# NexieControl_rev_2.net
KiCad netlist of a schematic drawn in Altium Designer
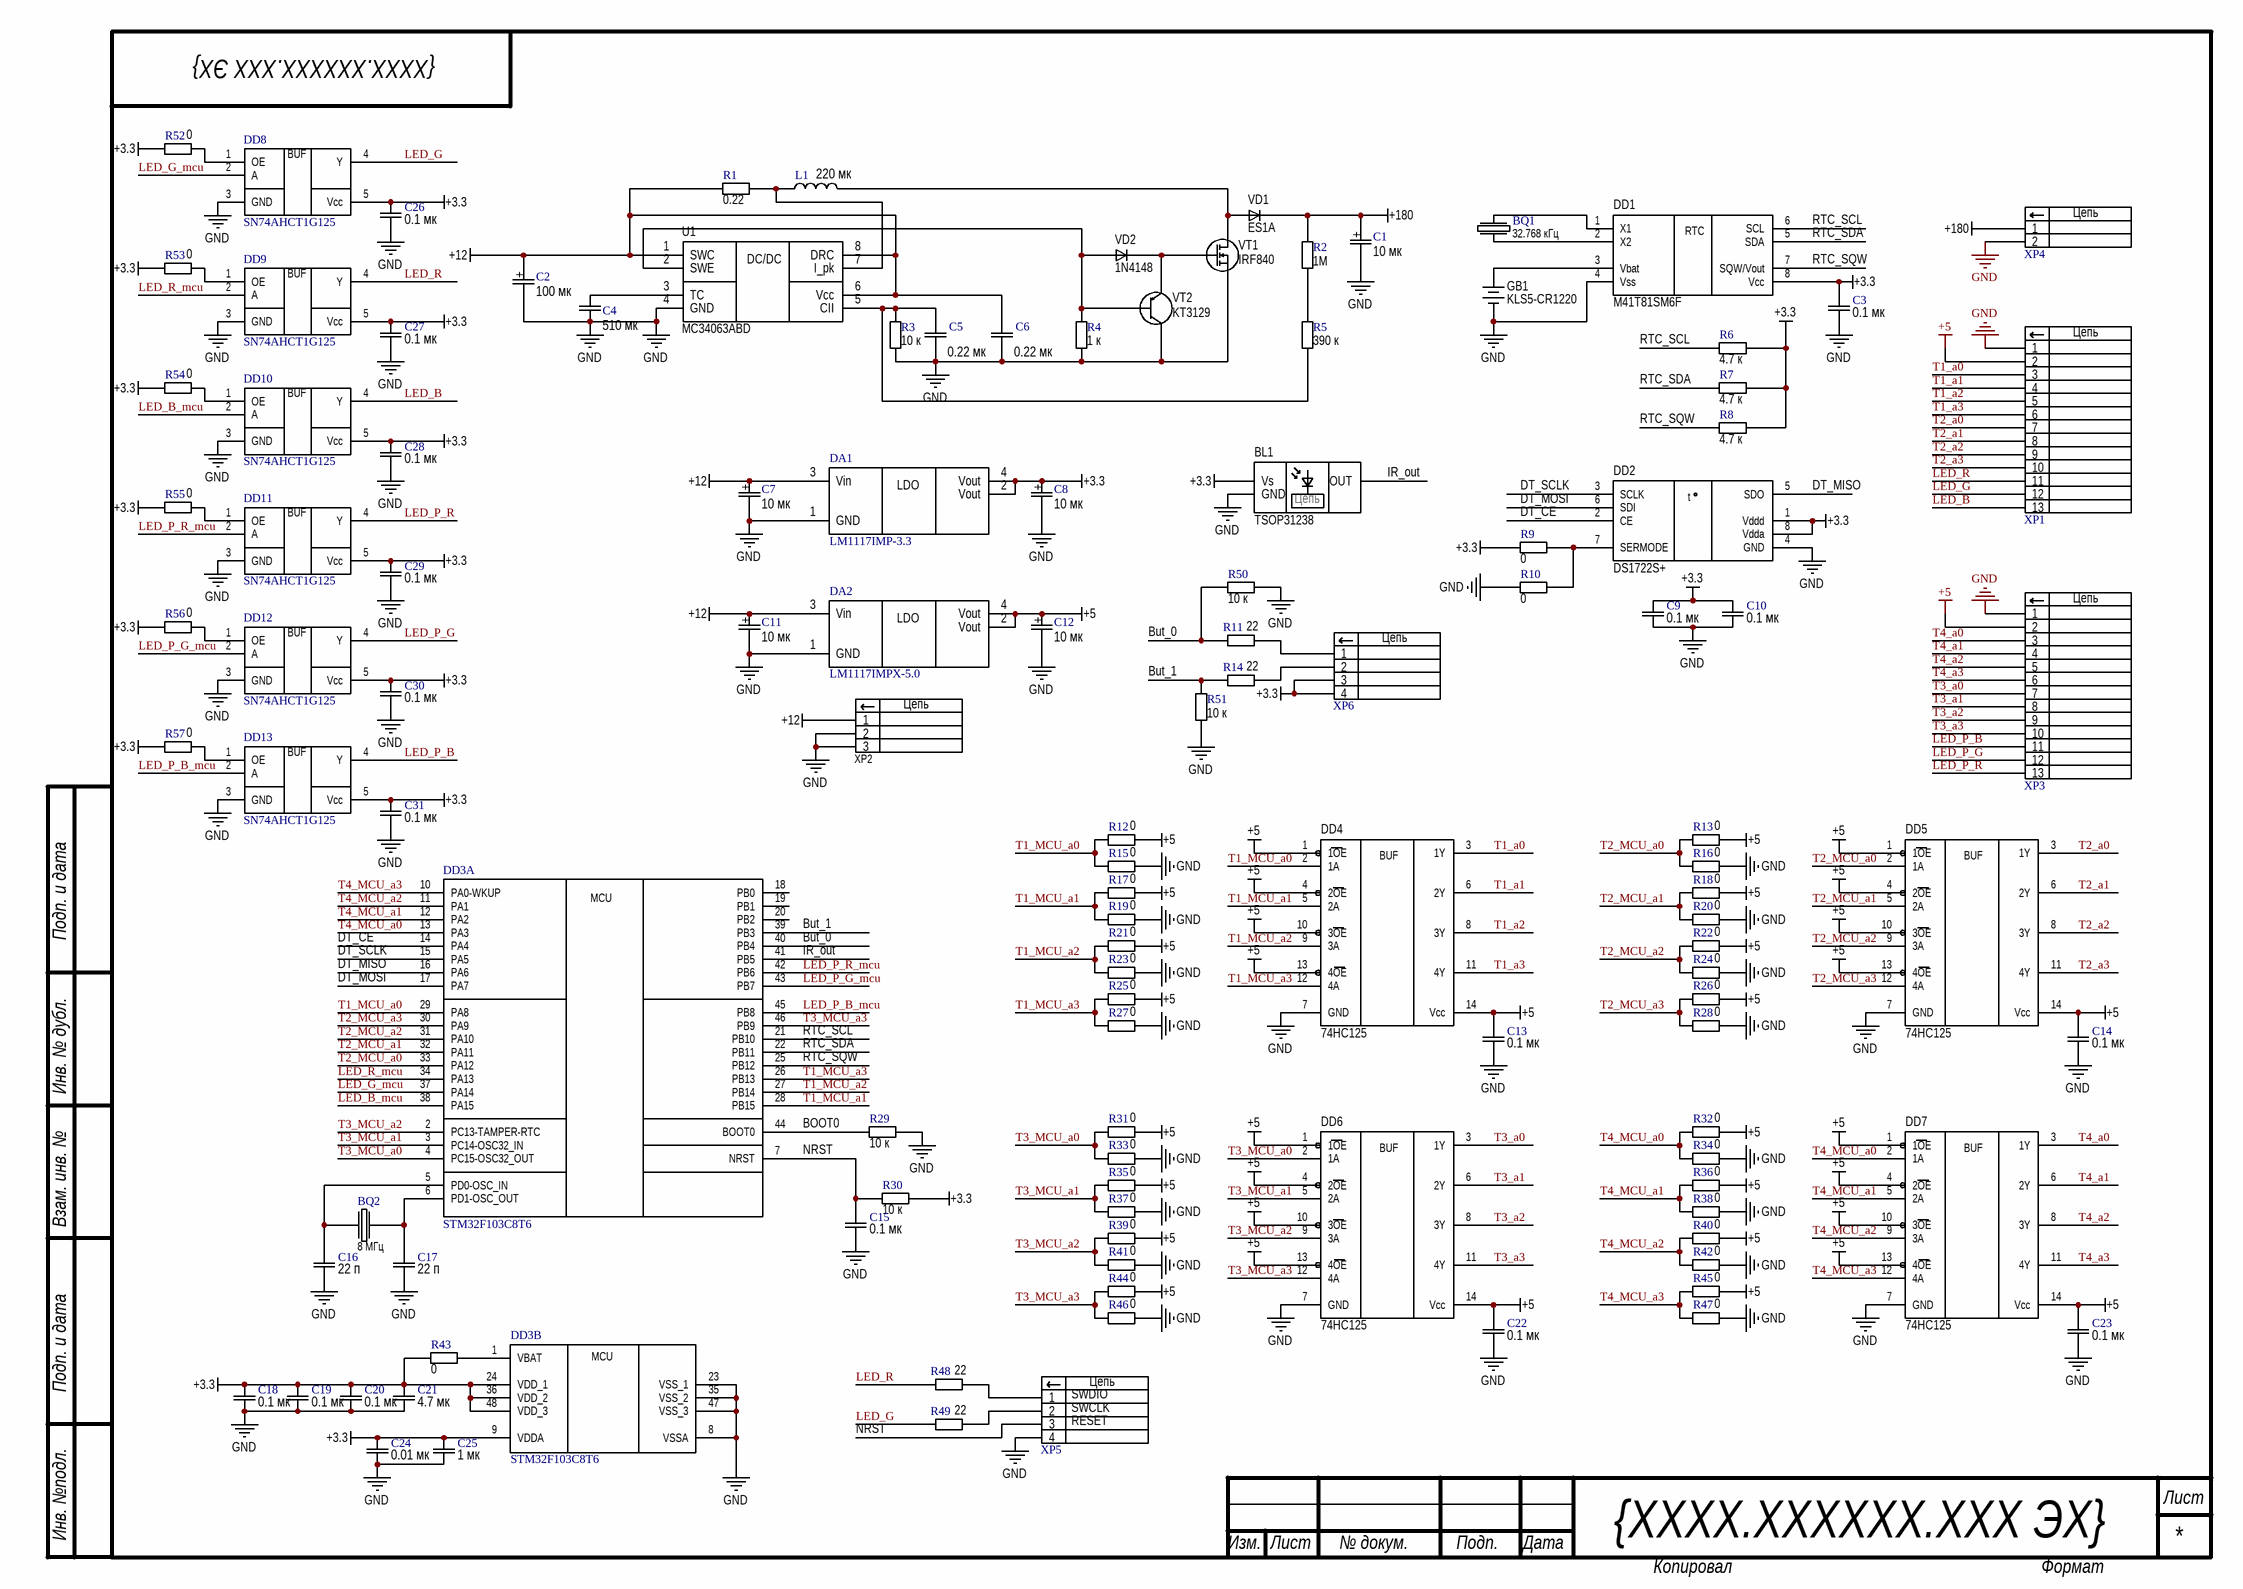
[diagram p0: NexieControl rev.2.SchDoc]

(export (version "E")
  (design (tool "Eeschema 10.0.6"))
  (components
    (comp (ref "BL1")
      (value "TSOP31238")
      (footprint "TSOP31238")
      (description "TSOP31238 (TSOP1738), ИК-приемник 38кГц")
      (fields (field (name "MANUFACTURER") "Vishay") (field (name "CREATOR") "FedorenkoSS"))
      (libsource (lib "Vishay") (part "TSOP31238"))
    )
    (comp (ref "BQ1")
      (value "9HT10")
      (footprint "9HT10")
      (fields
        (field (name "MANUFACTURER") "TXC Corporation")
        (field (name "FREQUENCY") "32.768 кГц")
        (field (name "CREATOR") "FedorenkoSS")
      )
      (libsource (lib "TXC_Corporation") (part "9HT10"))
    )
    (comp (ref "BQ2")
      (value "KX-9AT")
      (footprint "KX-9A")
      (fields
        (field (name "MANUFACTURER") "Geyer Electronic")
        (field (name "FREQUENCY") "8 МГц")
        (field (name "CREATOR") "PavelR")
      )
      (libsource (lib "Geyer") (part "KX-9AT"))
    )
    (comp (ref "C1")
      (value "10 мк")
      (footprint "K50-35(10x12)")
      (fields (field (name "Comment") "Polar capacitor") (field (name "CREATOR") "PavelR"))
      (libsource (lib "Capacitors") (part "Polar capacitor"))
    )
    (comp (ref "C2")
      (value "100 мк")
      (footprint "Tantal_SMD_A")
      (fields
        (field (name "MANUFACTURER") "Vishay")
        (field (name "Comment") "Polar capacitor")
        (field (name "CREATOR") "PavelR")
      )
      (libsource (lib "Capacitors") (part "Polar capacitor"))
    )
    (comp (ref "C3")
      (value "0.1 мк")
      (footprint "SMD_0603")
      (description "Capacitors")
      (fields (field (name "CREATOR") "PavelR"))
      (libsource (lib "Capacitors") (part "Capacitors"))
    )
    (comp (ref "C4")
      (value "510 мк")
      (footprint "SMD_0603")
      (description "Capacitors")
      (fields (field (name "CREATOR") "PavelR"))
      (libsource (lib "Capacitors") (part "Capacitors"))
    )
    (comp (ref "C5")
      (value "0.22 мк")
      (footprint "SMD_0603")
      (description "Capacitors")
      (fields (field (name "CREATOR") "PavelR"))
      (libsource (lib "Capacitors") (part "Capacitors"))
    )
    (comp (ref "C6")
      (value "0.22 мк")
      (footprint "SMD_0603")
      (description "Capacitors")
      (fields (field (name "CREATOR") "PavelR"))
      (libsource (lib "Capacitors") (part "Capacitors"))
    )
    (comp (ref "C7")
      (value "10 мк")
      (footprint "Tantal_SMD_C")
      (fields (field (name "Comment") "Polar capacitor") (field (name "CREATOR") "PavelR"))
      (libsource (lib "Capacitors") (part "Polar capacitor"))
    )
    (comp (ref "C8")
      (value "10 мк")
      (footprint "Tantal_SMD_A")
      (fields (field (name "Comment") "Polar capacitor") (field (name "CREATOR") "PavelR"))
      (libsource (lib "Capacitors") (part "Polar capacitor"))
    )
    (comp (ref "C9")
      (value "0.1 мк")
      (footprint "SMD_0603")
      (description "Capacitors")
      (fields (field (name "CREATOR") "PavelR"))
      (libsource (lib "Capacitors") (part "Capacitors"))
    )
    (comp (ref "C10")
      (value "0.1 мк")
      (footprint "SMD_0603")
      (description "Capacitors")
      (fields (field (name "CREATOR") "PavelR"))
      (libsource (lib "Capacitors") (part "Capacitors"))
    )
    (comp (ref "C11")
      (value "10 мк")
      (footprint "Tantal_SMD_C")
      (fields (field (name "Comment") "Polar capacitor") (field (name "CREATOR") "PavelR"))
      (libsource (lib "Capacitors") (part "Polar capacitor"))
    )
    (comp (ref "C12")
      (value "10 мк")
      (footprint "Tantal_SMD_A")
      (fields (field (name "Comment") "Polar capacitor") (field (name "CREATOR") "PavelR"))
      (libsource (lib "Capacitors") (part "Polar capacitor"))
    )
    (comp (ref "C13")
      (value "0.1 мк")
      (footprint "SMD_0603")
      (description "Capacitors")
      (fields (field (name "CREATOR") "PavelR"))
      (libsource (lib "Capacitors") (part "Capacitors"))
    )
    (comp (ref "C14")
      (value "0.1 мк")
      (footprint "SMD_0603")
      (description "Capacitors")
      (fields (field (name "CREATOR") "PavelR"))
      (libsource (lib "Capacitors") (part "Capacitors"))
    )
    (comp (ref "C15")
      (value "0.1 мк")
      (footprint "SMD_0603")
      (description "Capacitors")
      (fields (field (name "CREATOR") "PavelR"))
      (libsource (lib "Capacitors") (part "Capacitors"))
    )
    (comp (ref "C16")
      (value "22 п")
      (footprint "SMD_0603")
      (description "Capacitors")
      (fields (field (name "CREATOR") "PavelR"))
      (libsource (lib "Capacitors") (part "Capacitors"))
    )
    (comp (ref "C17")
      (value "22 п")
      (footprint "SMD_0603")
      (description "Capacitors")
      (fields (field (name "CREATOR") "PavelR"))
      (libsource (lib "Capacitors") (part "Capacitors"))
    )
    (comp (ref "C18")
      (value "0.1 мк")
      (footprint "SMD_0603")
      (description "Capacitors")
      (fields (field (name "CREATOR") "PavelR"))
      (libsource (lib "Capacitors") (part "Capacitors"))
    )
    (comp (ref "C19")
      (value "0.1 мк")
      (footprint "SMD_0603")
      (description "Capacitors")
      (fields (field (name "CREATOR") "PavelR"))
      (libsource (lib "Capacitors") (part "Capacitors"))
    )
    (comp (ref "C20")
      (value "0.1 мк")
      (footprint "SMD_0603")
      (description "Capacitors")
      (fields (field (name "CREATOR") "PavelR"))
      (libsource (lib "Capacitors") (part "Capacitors"))
    )
    (comp (ref "C21")
      (value "4.7 мк")
      (footprint "SMD_0603")
      (description "Capacitors")
      (fields (field (name "CREATOR") "PavelR"))
      (libsource (lib "Capacitors") (part "Capacitors"))
    )
    (comp (ref "C22")
      (value "0.1 мк")
      (footprint "SMD_0603")
      (description "Capacitors")
      (fields (field (name "CREATOR") "PavelR"))
      (libsource (lib "Capacitors") (part "Capacitors"))
    )
    (comp (ref "C23")
      (value "0.1 мк")
      (footprint "SMD_0603")
      (description "Capacitors")
      (fields (field (name "CREATOR") "PavelR"))
      (libsource (lib "Capacitors") (part "Capacitors"))
    )
    (comp (ref "C24")
      (value "0.01 мк")
      (footprint "SMD_0603")
      (description "Capacitors")
      (fields (field (name "CREATOR") "PavelR"))
      (libsource (lib "Capacitors") (part "Capacitors"))
    )
    (comp (ref "C25")
      (value "1 мк")
      (footprint "SMD_0603")
      (description "Capacitors")
      (fields (field (name "CREATOR") "PavelR"))
      (libsource (lib "Capacitors") (part "Capacitors"))
    )
    (comp (ref "C26")
      (value "0.1 мк")
      (footprint "SMD_0603")
      (description "Capacitors")
      (fields (field (name "CREATOR") "PavelR"))
      (libsource (lib "Capacitors") (part "Capacitors"))
    )
    (comp (ref "C27")
      (value "0.1 мк")
      (footprint "SMD_0603")
      (description "Capacitors")
      (fields (field (name "CREATOR") "PavelR"))
      (libsource (lib "Capacitors") (part "Capacitors"))
    )
    (comp (ref "C28")
      (value "0.1 мк")
      (footprint "SMD_0603")
      (description "Capacitors")
      (fields (field (name "CREATOR") "PavelR"))
      (libsource (lib "Capacitors") (part "Capacitors"))
    )
    (comp (ref "C29")
      (value "0.1 мк")
      (footprint "SMD_0603")
      (description "Capacitors")
      (fields (field (name "CREATOR") "PavelR"))
      (libsource (lib "Capacitors") (part "Capacitors"))
    )
    (comp (ref "C30")
      (value "0.1 мк")
      (footprint "SMD_0603")
      (description "Capacitors")
      (fields (field (name "CREATOR") "PavelR"))
      (libsource (lib "Capacitors") (part "Capacitors"))
    )
    (comp (ref "C31")
      (value "0.1 мк")
      (footprint "SMD_0603")
      (description "Capacitors")
      (fields (field (name "CREATOR") "PavelR"))
      (libsource (lib "Capacitors") (part "Capacitors"))
    )
    (comp (ref "DA1")
      (value "LM1117IMP-3.3")
      (footprint "S-PQFP-G64")
      (description "Стабилизатор напряжения LowDrop, +3.3В, 0.8А [SOT-223]")
      (fields (field (name "MANUFACTURER") "Texas Instruments") (field (name "CREATOR") "FedorenkoS"))
      (libsource (lib "TI_LDO") (part "LM1117IMP-3.3/NOPB"))
    )
    (comp (ref "DA2")
      (value "LM1117IMPX-5.0")
      (footprint "S-PQFP-G64")
      (description "Линейный регулятор с низким падением напряжения, 5В, 1.2А, [SOT-223]")
      (fields (field (name "MANUFACTURER") "Texas Instruments") (field (name "CREATOR") "FedorenkoS"))
      (libsource (lib "TI_LDO") (part "LM1117IMPX-5.0"))
    )
    (comp (ref "DD1")
      (value "M41T81SM6F")
      (footprint "Soic-8")
      (description "Часы реального времени, формат (дата/месяц/год сс:мм:чч), I2C, 2.7В...5.5В, [SOIC-8]")
      (fields (field (name "MANUFACTURER") "ST Microelectronics") (field (name "CREATOR") "FedorenkoSS"))
      (libsource (lib "STMicroelectronics") (part "M41T81SM6F"))
    )
    (comp (ref "DD2")
      (value "DS1722S+")
      (footprint "Soic-8")
      (description "DS1722\r\nDigital Thermometer with\r\nSPI/3-Wire Interface")
      (fields (field (name "MANUFACTURER") "Dallas_Semiconductor") (field (name "CREATOR") "FedorenkoSS"))
      (libsource (lib "Dallas_Semiconductor") (part "DS1722S+"))
    )
    (comp (ref "DD3")
      (value "STM32F103C8T6")
      (footprint "STM-LQFP48L")
      (fields (field (name "MANUFACTURER") "STMicroelectronix"))
      (libsource (lib "STM32F1") (part "STM32F103C8T6"))
    )
    (comp (ref "DD4")
      (value "74HC125")
      (footprint "Soic-14")
      (description "74HC125D.653, Буферы и линейные аппаратные драйверы QUAD 3-STATE BUS BUF [SO-14]")
      (fields (field (name "MANUFACTURER") "NXP Semiconductor") (field (name "CREATOR") "FedorenkoSS"))
      (libsource (lib "NXP_Semiconductor") (part "74HC125"))
    )
    (comp (ref "DD5")
      (value "74HC125")
      (footprint "Soic-14")
      (description "74HC125D.653, Буферы и линейные аппаратные драйверы QUAD 3-STATE BUS BUF [SO-14]")
      (fields (field (name "MANUFACTURER") "NXP Semiconductor") (field (name "CREATOR") "FedorenkoSS"))
      (libsource (lib "NXP_Semiconductor") (part "74HC125"))
    )
    (comp (ref "DD6")
      (value "74HC125")
      (footprint "Soic-14")
      (description "74HC125D.653, Буферы и линейные аппаратные драйверы QUAD 3-STATE BUS BUF [SO-14]")
      (fields (field (name "MANUFACTURER") "NXP Semiconductor") (field (name "CREATOR") "FedorenkoSS"))
      (libsource (lib "NXP_Semiconductor") (part "74HC125"))
    )
    (comp (ref "DD7")
      (value "74HC125")
      (footprint "Soic-14")
      (description "74HC125D.653, Буферы и линейные аппаратные драйверы QUAD 3-STATE BUS BUF [SO-14]")
      (fields (field (name "MANUFACTURER") "NXP Semiconductor") (field (name "CREATOR") "FedorenkoSS"))
      (libsource (lib "NXP_Semiconductor") (part "74HC125"))
    )
    (comp (ref "DD8")
      (value "SN74AHCT1G125")
      (footprint "SOT 23")
      (fields (field (name "MANUFACTURER") "Texas Instruments"))
      (libsource (lib "SN74AHCT1G125") (part "SN74AHCT1G125"))
    )
    (comp (ref "DD9")
      (value "SN74AHCT1G125")
      (footprint "SOT 23")
      (fields (field (name "MANUFACTURER") "Texas Instruments"))
      (libsource (lib "SN74AHCT1G125") (part "SN74AHCT1G125"))
    )
    (comp (ref "DD10")
      (value "SN74AHCT1G125")
      (footprint "SOT 23")
      (fields (field (name "MANUFACTURER") "Texas Instruments"))
      (libsource (lib "SN74AHCT1G125") (part "SN74AHCT1G125"))
    )
    (comp (ref "DD11")
      (value "SN74AHCT1G125")
      (footprint "SOT 23")
      (fields (field (name "MANUFACTURER") "Texas Instruments"))
      (libsource (lib "SN74AHCT1G125") (part "SN74AHCT1G125"))
    )
    (comp (ref "DD12")
      (value "SN74AHCT1G125")
      (footprint "SOT 23")
      (fields (field (name "MANUFACTURER") "Texas Instruments"))
      (libsource (lib "SN74AHCT1G125") (part "SN74AHCT1G125"))
    )
    (comp (ref "DD13")
      (value "SN74AHCT1G125")
      (footprint "SOT 23")
      (fields (field (name "MANUFACTURER") "Texas Instruments"))
      (libsource (lib "SN74AHCT1G125") (part "SN74AHCT1G125"))
    )
    (comp (ref "GB1")
      (value "KLS5-CR1220")
      (footprint "KLS5-CR1220-01")
      (description "KLS5-CR1220-01 (FC1-5010), Батарейный отсек 1xCR1220")
      (fields (field (name "MANUFACTURER") "KLS electronic co ltd") (field (name "CREATOR") "FedorenkoSS"))
      (libsource (lib "Battery") (part "KLS5-CR1220"))
    )
    (comp (ref "L1")
      (value "220 мк")
      (footprint "2220")
      (fields (field (name "Comment") "Inductor") (field (name "CREATER") "FedorenkoS"))
      (libsource (lib "SMD_inductors") (part "Inductor"))
    )
    (comp (ref "R1")
      (value "0.22")
      (footprint "SMD_2512")
      (fields
        (field (name "MANUFACTURER") "Yageo")
        (field (name "Comment") "Resistor")
        (field (name "CREATOR") "PavelR")
      )
      (libsource (lib "") (part "Resistor_1"))
    )
    (comp (ref "R2")
      (value "1М")
      (footprint "SMD_0805")
      (fields (field (name "Comment") "Resistor") (field (name "CREATOR") "PavelR"))
      (libsource (lib "") (part "Resistor_2"))
    )
    (comp (ref "R3")
      (value "10 к")
      (footprint "SMD_0603")
      (fields (field (name "Comment") "Resistor") (field (name "CREATOR") "PavelR"))
      (libsource (lib "") (part "Resistor_2"))
    )
    (comp (ref "R4")
      (value "1 к")
      (footprint "SMD_0603")
      (fields (field (name "Comment") "Resistor") (field (name "CREATOR") "PavelR"))
      (libsource (lib "") (part "Resistor_2"))
    )
    (comp (ref "R5")
      (value "390 к")
      (footprint "SMD_0805")
      (fields (field (name "Comment") "Resistor") (field (name "CREATOR") "PavelR"))
      (libsource (lib "") (part "Resistor_2"))
    )
    (comp (ref "R6")
      (value "4.7 к")
      (footprint "SMD_0603")
      (fields (field (name "Comment") "Resistor") (field (name "CREATOR") "PavelR"))
      (libsource (lib "Resistors") (part "Resistor"))
    )
    (comp (ref "R7")
      (value "4.7 к")
      (footprint "SMD_0603")
      (fields (field (name "Comment") "Resistor") (field (name "CREATOR") "PavelR"))
      (libsource (lib "Resistors") (part "Resistor"))
    )
    (comp (ref "R8")
      (value "4.7 к")
      (footprint "SMD_0603")
      (fields (field (name "Comment") "Resistor") (field (name "CREATOR") "PavelR"))
      (libsource (lib "Resistors") (part "Resistor"))
    )
    (comp (ref "R9")
      (value "0")
      (footprint "SMD_0603")
      (fields (field (name "Comment") "Resistor") (field (name "CREATOR") "PavelR"))
      (libsource (lib "") (part "Resistor_1"))
    )
    (comp (ref "R10")
      (value "0")
      (footprint "SMD_0603")
      (fields (field (name "Comment") "Resistor") (field (name "CREATOR") "PavelR"))
      (libsource (lib "Resistors") (part "Resistor"))
    )
    (comp (ref "R11")
      (value "22")
      (footprint "SMD_0603")
      (fields (field (name "Comment") "Resistor") (field (name "CREATOR") "PavelR"))
      (libsource (lib "Resistors") (part "Resistor"))
    )
    (comp (ref "R12")
      (value "0")
      (footprint "SMD_0603")
      (fields (field (name "Comment") "Resistor") (field (name "CREATOR") "PavelR"))
      (libsource (lib "") (part "Resistor_1"))
    )
    (comp (ref "R13")
      (value "0")
      (footprint "SMD_0603")
      (fields (field (name "Comment") "Resistor") (field (name "CREATOR") "PavelR"))
      (libsource (lib "") (part "Resistor_1"))
    )
    (comp (ref "R14")
      (value "22")
      (footprint "SMD_0603")
      (fields (field (name "Comment") "Resistor") (field (name "CREATOR") "PavelR"))
      (libsource (lib "Resistors") (part "Resistor"))
    )
    (comp (ref "R15")
      (value "0")
      (footprint "SMD_0603")
      (fields (field (name "Comment") "Resistor") (field (name "CREATOR") "PavelR"))
      (libsource (lib "Resistors") (part "Resistor"))
    )
    (comp (ref "R16")
      (value "0")
      (footprint "SMD_0603")
      (fields (field (name "Comment") "Resistor") (field (name "CREATOR") "PavelR"))
      (libsource (lib "Resistors") (part "Resistor"))
    )
    (comp (ref "R17")
      (value "0")
      (footprint "SMD_0603")
      (fields (field (name "Comment") "Resistor") (field (name "CREATOR") "PavelR"))
      (libsource (lib "") (part "Resistor_1"))
    )
    (comp (ref "R18")
      (value "0")
      (footprint "SMD_0603")
      (fields (field (name "Comment") "Resistor") (field (name "CREATOR") "PavelR"))
      (libsource (lib "") (part "Resistor_1"))
    )
    (comp (ref "R19")
      (value "0")
      (footprint "SMD_0603")
      (fields (field (name "Comment") "Resistor") (field (name "CREATOR") "PavelR"))
      (libsource (lib "Resistors") (part "Resistor"))
    )
    (comp (ref "R20")
      (value "0")
      (footprint "SMD_0603")
      (fields (field (name "Comment") "Resistor") (field (name "CREATOR") "PavelR"))
      (libsource (lib "Resistors") (part "Resistor"))
    )
    (comp (ref "R21")
      (value "0")
      (footprint "SMD_0603")
      (fields (field (name "Comment") "Resistor") (field (name "CREATOR") "PavelR"))
      (libsource (lib "") (part "Resistor_1"))
    )
    (comp (ref "R22")
      (value "0")
      (footprint "SMD_0603")
      (fields (field (name "Comment") "Resistor") (field (name "CREATOR") "PavelR"))
      (libsource (lib "") (part "Resistor_1"))
    )
    (comp (ref "R23")
      (value "0")
      (footprint "SMD_0603")
      (fields (field (name "Comment") "Resistor") (field (name "CREATOR") "PavelR"))
      (libsource (lib "Resistors") (part "Resistor"))
    )
    (comp (ref "R24")
      (value "0")
      (footprint "SMD_0603")
      (fields (field (name "Comment") "Resistor") (field (name "CREATOR") "PavelR"))
      (libsource (lib "Resistors") (part "Resistor"))
    )
    (comp (ref "R25")
      (value "0")
      (footprint "SMD_0603")
      (fields (field (name "Comment") "Resistor") (field (name "CREATOR") "PavelR"))
      (libsource (lib "") (part "Resistor_1"))
    )
    (comp (ref "R26")
      (value "0")
      (footprint "SMD_0603")
      (fields (field (name "Comment") "Resistor") (field (name "CREATOR") "PavelR"))
      (libsource (lib "") (part "Resistor_1"))
    )
    (comp (ref "R27")
      (value "0")
      (footprint "SMD_0603")
      (fields (field (name "Comment") "Resistor") (field (name "CREATOR") "PavelR"))
      (libsource (lib "Resistors") (part "Resistor"))
    )
    (comp (ref "R28")
      (value "0")
      (footprint "SMD_0603")
      (fields (field (name "Comment") "Resistor") (field (name "CREATOR") "PavelR"))
      (libsource (lib "Resistors") (part "Resistor"))
    )
    (comp (ref "R29")
      (value "10 к")
      (footprint "SMD_0603")
      (fields (field (name "Comment") "Resistor") (field (name "CREATOR") "PavelR"))
      (libsource (lib "") (part "Resistor_1"))
    )
    (comp (ref "R30")
      (value "10 к")
      (footprint "SMD_0603")
      (fields (field (name "Comment") "Resistor") (field (name "CREATOR") "PavelR"))
      (libsource (lib "Resistors") (part "Resistor"))
    )
    (comp (ref "R31")
      (value "0")
      (footprint "SMD_0603")
      (fields (field (name "Comment") "Resistor") (field (name "CREATOR") "PavelR"))
      (libsource (lib "") (part "Resistor_1"))
    )
    (comp (ref "R32")
      (value "0")
      (footprint "SMD_0603")
      (fields (field (name "Comment") "Resistor") (field (name "CREATOR") "PavelR"))
      (libsource (lib "") (part "Resistor_1"))
    )
    (comp (ref "R33")
      (value "0")
      (footprint "SMD_0603")
      (fields (field (name "Comment") "Resistor") (field (name "CREATOR") "PavelR"))
      (libsource (lib "Resistors") (part "Resistor"))
    )
    (comp (ref "R34")
      (value "0")
      (footprint "SMD_0603")
      (fields (field (name "Comment") "Resistor") (field (name "CREATOR") "PavelR"))
      (libsource (lib "Resistors") (part "Resistor"))
    )
    (comp (ref "R35")
      (value "0")
      (footprint "SMD_0603")
      (fields (field (name "Comment") "Resistor") (field (name "CREATOR") "PavelR"))
      (libsource (lib "") (part "Resistor_1"))
    )
    (comp (ref "R36")
      (value "0")
      (footprint "SMD_0603")
      (fields (field (name "Comment") "Resistor") (field (name "CREATOR") "PavelR"))
      (libsource (lib "") (part "Resistor_1"))
    )
    (comp (ref "R37")
      (value "0")
      (footprint "SMD_0603")
      (fields (field (name "Comment") "Resistor") (field (name "CREATOR") "PavelR"))
      (libsource (lib "Resistors") (part "Resistor"))
    )
    (comp (ref "R38")
      (value "0")
      (footprint "SMD_0603")
      (fields (field (name "Comment") "Resistor") (field (name "CREATOR") "PavelR"))
      (libsource (lib "Resistors") (part "Resistor"))
    )
    (comp (ref "R39")
      (value "0")
      (footprint "SMD_0603")
      (fields (field (name "Comment") "Resistor") (field (name "CREATOR") "PavelR"))
      (libsource (lib "") (part "Resistor_1"))
    )
    (comp (ref "R40")
      (value "0")
      (footprint "SMD_0603")
      (fields (field (name "Comment") "Resistor") (field (name "CREATOR") "PavelR"))
      (libsource (lib "") (part "Resistor_1"))
    )
    (comp (ref "R41")
      (value "0")
      (footprint "SMD_0603")
      (fields (field (name "Comment") "Resistor") (field (name "CREATOR") "PavelR"))
      (libsource (lib "Resistors") (part "Resistor"))
    )
    (comp (ref "R42")
      (value "0")
      (footprint "SMD_0603")
      (fields (field (name "Comment") "Resistor") (field (name "CREATOR") "PavelR"))
      (libsource (lib "Resistors") (part "Resistor"))
    )
    (comp (ref "R43")
      (value "0")
      (footprint "SMD_0603")
      (fields (field (name "Comment") "Resistor") (field (name "CREATOR") "PavelR"))
      (libsource (lib "") (part "Resistor_1"))
    )
    (comp (ref "R44")
      (value "0")
      (footprint "SMD_0603")
      (fields (field (name "Comment") "Resistor") (field (name "CREATOR") "PavelR"))
      (libsource (lib "") (part "Resistor_1"))
    )
    (comp (ref "R45")
      (value "0")
      (footprint "SMD_0603")
      (fields (field (name "Comment") "Resistor") (field (name "CREATOR") "PavelR"))
      (libsource (lib "") (part "Resistor_1"))
    )
    (comp (ref "R46")
      (value "0")
      (footprint "SMD_0603")
      (fields (field (name "Comment") "Resistor") (field (name "CREATOR") "PavelR"))
      (libsource (lib "Resistors") (part "Resistor"))
    )
    (comp (ref "R47")
      (value "0")
      (footprint "SMD_0603")
      (fields (field (name "Comment") "Resistor") (field (name "CREATOR") "PavelR"))
      (libsource (lib "Resistors") (part "Resistor"))
    )
    (comp (ref "R48")
      (value "22")
      (footprint "SMD_0603")
      (fields (field (name "Comment") "Resistor") (field (name "CREATOR") "PavelR"))
      (libsource (lib "Resistors") (part "Resistor"))
    )
    (comp (ref "R49")
      (value "22")
      (footprint "SMD_0603")
      (fields (field (name "Comment") "Resistor") (field (name "CREATOR") "PavelR"))
      (libsource (lib "Resistors") (part "Resistor"))
    )
    (comp (ref "R50")
      (value "10 к")
      (footprint "SMD_0603")
      (fields (field (name "Comment") "Resistor") (field (name "CREATOR") "PavelR"))
      (libsource (lib "") (part "Resistor_1"))
    )
    (comp (ref "R51")
      (value "10 к")
      (footprint "SMD_0603")
      (fields (field (name "Comment") "Resistor") (field (name "CREATOR") "PavelR"))
      (libsource (lib "") (part "Resistor_2"))
    )
    (comp (ref "R52")
      (value "0")
      (footprint "SMD_0603")
      (fields (field (name "Comment") "Resistor") (field (name "CREATOR") "PavelR"))
      (libsource (lib "") (part "Resistor_1"))
    )
    (comp (ref "R53")
      (value "0")
      (footprint "SMD_0603")
      (fields (field (name "Comment") "Resistor") (field (name "CREATOR") "PavelR"))
      (libsource (lib "") (part "Resistor_1"))
    )
    (comp (ref "R54")
      (value "0")
      (footprint "SMD_0603")
      (fields (field (name "Comment") "Resistor") (field (name "CREATOR") "PavelR"))
      (libsource (lib "") (part "Resistor_1"))
    )
    (comp (ref "R55")
      (value "0")
      (footprint "SMD_0603")
      (fields (field (name "Comment") "Resistor") (field (name "CREATOR") "PavelR"))
      (libsource (lib "") (part "Resistor_1"))
    )
    (comp (ref "R56")
      (value "0")
      (footprint "SMD_0603")
      (fields (field (name "Comment") "Resistor") (field (name "CREATOR") "PavelR"))
      (libsource (lib "") (part "Resistor_1"))
    )
    (comp (ref "R57")
      (value "0")
      (footprint "SMD_0603")
      (fields (field (name "Comment") "Resistor") (field (name "CREATOR") "PavelR"))
      (libsource (lib "") (part "Resistor_1"))
    )
    (comp (ref "U1")
      (value "MC34063ABD")
      (footprint "SO-8")
      (fields (field (name "MANUFACTURER") "ST Microelectronics"))
      (libsource (lib "STM_DC-DC") (part "MC34063ABD"))
    )
    (comp (ref "VD1")
      (value "ES1A")
      (footprint "DO_214AC")
      (description "ES1J, Диод быстродействующий 1А 600В 35нс [SMA / DO-214AC]")
      (fields (field (name "MANUFACTURER") "DC COMPONENTS CO., LTD.") (field (name "CREATOR") "FedorenkoSS"))
      (libsource (lib "Diodes") (part "ES1A"))
    )
    (comp (ref "VD2")
      (value "1N4148")
      (footprint "SOD-323")
      (fields (field (name "MANUFACTURER") "Vishay") (field (name "CREATOR") "FedorenkoSS"))
      (libsource (lib "Diodes") (part "1N4148"))
    )
    (comp (ref "VT1")
      (value "IRF840")
      (footprint "D2_PAK")
      (description "Транзистор, N-канал 500В 8.0А")
      (fields (field (name "MANUFACTURER") "Vishay") (field (name "CREATOR") "FedorenkoS"))
      (libsource (lib "Tranzistors") (part "IRF840ASPBF"))
    )
    (comp (ref "VT2")
      (value "KT3129")
      (footprint "SOT-23")
      (fields (field (name "MANUFACTURER") "Россия") (field (name "CREATOR") "FedorenkoS"))
      (libsource (lib "Tranzistors") (part "KT3129"))
    )
    (comp (ref "XP1")
      (value "DS1021-1*13SF11")
      (footprint "DS1021-1*13")
      (description "PLS")
      (fields (field (name "РАЗРАБОТЧИК БИБЛИОТЕКИ") "Федоренко С.С."))
      (libsource (lib "Connectors") (part "DS1021-1*13SF11"))
    )
    (comp (ref "XP2")
      (value "Power_jack")
      (footprint "DC_Power_Jack")
      (libsource (lib "Connectors") (part "Power_jack"))
    )
    (comp (ref "XP3")
      (value "DS1021-1*13SF11")
      (footprint "DS1021-1*13")
      (description "PLS")
      (fields (field (name "РАЗРАБОТЧИК БИБЛИОТЕКИ") "Федоренко С.С."))
      (libsource (lib "Connectors") (part "DS1021-1*13SF11"))
    )
    (comp (ref "XP4")
      (value "DS1021-1*2SF11")
      (footprint "DS1021-1*2")
      (description "PLS")
      (fields (field (name "РАЗРАБОТЧИК БИБЛИОТЕКИ") "Федоренко С.С."))
      (libsource (lib "Connectors") (part "DS1021-1*2SF11"))
    )
    (comp (ref "XP5")
      (value "DS1021-1*4SF11")
      (footprint "DS1021-1*4")
      (description "PLS")
      (fields (field (name "РАЗРАБОТЧИК БИБЛИОТЕКИ") "Федоренко С.С."))
      (libsource (lib "Connectors") (part "DS1021-1*4SF11"))
    )
    (comp (ref "XP6")
      (value "DS1021-1*4SF11")
      (footprint "DS1021-1*4")
      (description "PLS")
      (fields (field (name "РАЗРАБОТЧИК БИБЛИОТЕКИ") "Федоренко С.С."))
      (libsource (lib "Connectors") (part "DS1021-1*4SF11"))
    )
  )
  (nets
    (net (code "1") (name "+3.3") (class "Default")
      (node (ref "BL1") (pin "2") (pinfunction "Vs_2") (pintype "passive"))
      (node (ref "C10") (pin "2") (pinfunction "2_2") (pintype "passive"))
      (node (ref "C18") (pin "2") (pinfunction "2_2") (pintype "passive"))
      (node (ref "C19") (pin "2") (pinfunction "2_2") (pintype "passive"))
      (node (ref "C20") (pin "2") (pinfunction "2_2") (pintype "passive"))
      (node (ref "C21") (pin "2") (pinfunction "2_2") (pintype "passive"))
      (node (ref "C24") (pin "2") (pinfunction "2_2") (pintype "passive"))
      (node (ref "C25") (pin "2") (pinfunction "2_2") (pintype "passive"))
      (node (ref "C26") (pin "2") (pinfunction "2_2") (pintype "passive"))
      (node (ref "C27") (pin "2") (pinfunction "2_2") (pintype "passive"))
      (node (ref "C28") (pin "2") (pinfunction "2_2") (pintype "passive"))
      (node (ref "C29") (pin "2") (pinfunction "2_2") (pintype "passive"))
      (node (ref "C3") (pin "2") (pinfunction "2_2") (pintype "passive"))
      (node (ref "C30") (pin "2") (pinfunction "2_2") (pintype "passive"))
      (node (ref "C31") (pin "2") (pinfunction "2_2") (pintype "passive"))
      (node (ref "C8") (pin "1") (pinfunction "1_1") (pintype "passive"))
      (node (ref "C9") (pin "2") (pinfunction "2_2") (pintype "passive"))
      (node (ref "DA1") (pin "2") (pinfunction "Vout_2") (pintype "passive"))
      (node (ref "DA1") (pin "4") (pinfunction "Vout_4") (pintype "passive"))
      (node (ref "DD1") (pin "8") (pinfunction "Vcc_8") (pintype "power_in"))
      (node (ref "DD10") (pin "5") (pinfunction "Vcc_5") (pintype "passive"))
      (node (ref "DD11") (pin "5") (pinfunction "Vcc_5") (pintype "passive"))
      (node (ref "DD12") (pin "5") (pinfunction "Vcc_5") (pintype "passive"))
      (node (ref "DD13") (pin "5") (pinfunction "Vcc_5") (pintype "passive"))
      (node (ref "DD2") (pin "1") (pinfunction "Vddd_1") (pintype "power_in"))
      (node (ref "DD2") (pin "8") (pinfunction "Vdda_8") (pintype "power_in"))
      (node (ref "DD3") (pin "24") (pinfunction "VDD_1_24") (pintype "power_in"))
      (node (ref "DD3") (pin "36") (pinfunction "VDD_2_36") (pintype "power_in"))
      (node (ref "DD3") (pin "48") (pinfunction "VDD_3_48") (pintype "power_in"))
      (node (ref "DD3") (pin "9") (pinfunction "VDDA_9") (pintype "power_in"))
      (node (ref "DD8") (pin "5") (pinfunction "Vcc_5") (pintype "passive"))
      (node (ref "DD9") (pin "5") (pinfunction "Vcc_5") (pintype "passive"))
      (node (ref "R30") (pin "1") (pinfunction "1_1") (pintype "passive"))
      (node (ref "R43") (pin "1") (pinfunction "1_1") (pintype "passive"))
      (node (ref "R52") (pin "1") (pinfunction "1_1") (pintype "passive"))
      (node (ref "R53") (pin "1") (pinfunction "1_1") (pintype "passive"))
      (node (ref "R54") (pin "1") (pinfunction "1_1") (pintype "passive"))
      (node (ref "R55") (pin "1") (pinfunction "1_1") (pintype "passive"))
      (node (ref "R56") (pin "1") (pinfunction "1_1") (pintype "passive"))
      (node (ref "R57") (pin "1") (pinfunction "1_1") (pintype "passive"))
      (node (ref "R6") (pin "1") (pinfunction "1_1") (pintype "passive"))
      (node (ref "R7") (pin "1") (pinfunction "1_1") (pintype "passive"))
      (node (ref "R8") (pin "1") (pinfunction "1_1") (pintype "passive"))
      (node (ref "R9") (pin "1") (pinfunction "1_1") (pintype "passive"))
      (node (ref "XP6") (pin "3") (pinfunction "3_3") (pintype "passive"))
      (node (ref "XP6") (pin "4") (pinfunction "4_4") (pintype "passive"))
    )
    (net (code "2") (name "+5") (class "Default")
      (node (ref "C12") (pin "1") (pinfunction "1_1") (pintype "passive"))
      (node (ref "C13") (pin "2") (pinfunction "2_2") (pintype "passive"))
      (node (ref "C14") (pin "2") (pinfunction "2_2") (pintype "passive"))
      (node (ref "C22") (pin "2") (pinfunction "2_2") (pintype "passive"))
      (node (ref "C23") (pin "2") (pinfunction "2_2") (pintype "passive"))
      (node (ref "DA2") (pin "2") (pinfunction "Vout_2") (pintype "passive"))
      (node (ref "DA2") (pin "4") (pinfunction "Vout_4") (pintype "passive"))
      (node (ref "DD4") (pin "1") (pinfunction "1OE_1") (pintype "power_in"))
      (node (ref "DD4") (pin "10") (pinfunction "3OE_10") (pintype "power_in"))
      (node (ref "DD4") (pin "13") (pinfunction "4OE_13") (pintype "power_in"))
      (node (ref "DD4") (pin "14") (pinfunction "Vcc_14") (pintype "power_in"))
      (node (ref "DD4") (pin "4") (pinfunction "2OE_4") (pintype "power_in"))
      (node (ref "DD5") (pin "1") (pinfunction "1OE_1") (pintype "power_in"))
      (node (ref "DD5") (pin "10") (pinfunction "3OE_10") (pintype "power_in"))
      (node (ref "DD5") (pin "13") (pinfunction "4OE_13") (pintype "power_in"))
      (node (ref "DD5") (pin "14") (pinfunction "Vcc_14") (pintype "power_in"))
      (node (ref "DD5") (pin "4") (pinfunction "2OE_4") (pintype "power_in"))
      (node (ref "DD6") (pin "1") (pinfunction "1OE_1") (pintype "power_in"))
      (node (ref "DD6") (pin "10") (pinfunction "3OE_10") (pintype "power_in"))
      (node (ref "DD6") (pin "13") (pinfunction "4OE_13") (pintype "power_in"))
      (node (ref "DD6") (pin "14") (pinfunction "Vcc_14") (pintype "power_in"))
      (node (ref "DD6") (pin "4") (pinfunction "2OE_4") (pintype "power_in"))
      (node (ref "DD7") (pin "1") (pinfunction "1OE_1") (pintype "power_in"))
      (node (ref "DD7") (pin "10") (pinfunction "3OE_10") (pintype "power_in"))
      (node (ref "DD7") (pin "13") (pinfunction "4OE_13") (pintype "power_in"))
      (node (ref "DD7") (pin "14") (pinfunction "Vcc_14") (pintype "power_in"))
      (node (ref "DD7") (pin "4") (pinfunction "2OE_4") (pintype "power_in"))
      (node (ref "R12") (pin "2") (pinfunction "2_2") (pintype "passive"))
      (node (ref "R13") (pin "2") (pinfunction "2_2") (pintype "passive"))
      (node (ref "R17") (pin "2") (pinfunction "2_2") (pintype "passive"))
      (node (ref "R18") (pin "2") (pinfunction "2_2") (pintype "passive"))
      (node (ref "R21") (pin "2") (pinfunction "2_2") (pintype "passive"))
      (node (ref "R22") (pin "2") (pinfunction "2_2") (pintype "passive"))
      (node (ref "R25") (pin "2") (pinfunction "2_2") (pintype "passive"))
      (node (ref "R26") (pin "2") (pinfunction "2_2") (pintype "passive"))
      (node (ref "R31") (pin "2") (pinfunction "2_2") (pintype "passive"))
      (node (ref "R32") (pin "2") (pinfunction "2_2") (pintype "passive"))
      (node (ref "R35") (pin "2") (pinfunction "2_2") (pintype "passive"))
      (node (ref "R36") (pin "2") (pinfunction "2_2") (pintype "passive"))
      (node (ref "R39") (pin "2") (pinfunction "2_2") (pintype "passive"))
      (node (ref "R40") (pin "2") (pinfunction "2_2") (pintype "passive"))
      (node (ref "R44") (pin "2") (pinfunction "2_2") (pintype "passive"))
      (node (ref "R45") (pin "2") (pinfunction "2_2") (pintype "passive"))
      (node (ref "XP1") (pin "2") (pinfunction "2_2") (pintype "passive"))
      (node (ref "XP3") (pin "2") (pinfunction "2_2") (pintype "passive"))
    )
    (net (code "3") (name "+12") (class "Default")
      (node (ref "C11") (pin "1") (pinfunction "1_1") (pintype "passive"))
      (node (ref "C2") (pin "1") (pinfunction "1_1") (pintype "passive"))
      (node (ref "C6") (pin "2") (pinfunction "2_2") (pintype "passive"))
      (node (ref "C7") (pin "1") (pinfunction "1_1") (pintype "passive"))
      (node (ref "DA1") (pin "3") (pinfunction "Vin_3") (pintype "passive"))
      (node (ref "DA2") (pin "3") (pinfunction "Vin_3") (pintype "passive"))
      (node (ref "R1") (pin "1") (pinfunction "1_1") (pintype "passive"))
      (node (ref "U1") (pin "1") (pinfunction "SWC_1") (pintype "passive"))
      (node (ref "U1") (pin "6") (pinfunction "Vcc_6") (pintype "passive"))
      (node (ref "U1") (pin "8") (pinfunction "DRC_8") (pintype "passive"))
      (node (ref "XP2") (pin "1") (pinfunction "1_1") (pintype "passive"))
    )
    (net (code "4") (name "+180") (class "Default")
      (node (ref "C1") (pin "1") (pinfunction "1_1") (pintype "passive"))
      (node (ref "R2") (pin "2") (pinfunction "2_2") (pintype "passive"))
      (node (ref "VD1") (pin "2") (pinfunction "K_2") (pintype "passive"))
      (node (ref "XP4") (pin "1") (pinfunction "1_1") (pintype "passive"))
    )
    (net (code "5") (name "/BOOT0") (class "Default")
      (node (ref "DD3") (pin "44") (pinfunction "BOOT0_44") (pintype "passive"))
      (node (ref "R29") (pin "1") (pinfunction "1_1") (pintype "passive"))
    )
    (net (code "6") (name "/But_0") (class "Default")
      (node (ref "DD3") (pin "40") (pinfunction "PB4_40") (pintype "passive"))
      (node (ref "R11") (pin "2") (pinfunction "2_2") (pintype "passive"))
      (node (ref "R50") (pin "1") (pinfunction "1_1") (pintype "passive"))
    )
    (net (code "7") (name "/But_1") (class "Default")
      (node (ref "DD3") (pin "39") (pinfunction "PB3_39") (pintype "passive"))
      (node (ref "R14") (pin "2") (pinfunction "2_2") (pintype "passive"))
      (node (ref "R51") (pin "2") (pinfunction "2_2") (pintype "passive"))
    )
    (net (code "8") (name "/DT_CE") (class "Default")
      (node (ref "DD2") (pin "2") (pinfunction "CE_2") (pintype "power_in"))
      (node (ref "DD3") (pin "14") (pinfunction "PA4_14") (pintype "passive"))
    )
    (net (code "9") (name "/DT_MISO") (class "Default")
      (node (ref "DD2") (pin "5") (pinfunction "SDO_5") (pintype "power_in"))
      (node (ref "DD3") (pin "16") (pinfunction "PA6_16") (pintype "passive"))
    )
    (net (code "10") (name "/DT_MOSI") (class "Default")
      (node (ref "DD2") (pin "6") (pinfunction "SDI_6") (pintype "power_in"))
      (node (ref "DD3") (pin "17") (pinfunction "PA7_17") (pintype "passive"))
    )
    (net (code "11") (name "/DT_SCLK") (class "Default")
      (node (ref "DD2") (pin "3") (pinfunction "SCLK_3") (pintype "power_in"))
      (node (ref "DD3") (pin "15") (pinfunction "PA5_15") (pintype "passive"))
    )
    (net (code "12") (name "/IR_out") (class "Default")
      (node (ref "BL1") (pin "3") (pinfunction "OUT_3") (pintype "passive"))
      (node (ref "DD3") (pin "41") (pinfunction "PB5_41") (pintype "passive"))
    )
    (net (code "13") (name "/LED_B") (class "Default")
      (node (ref "DD10") (pin "4") (pinfunction "Y_4") (pintype "passive"))
      (node (ref "XP1") (pin "13") (pinfunction "13_13") (pintype "passive"))
    )
    (net (code "14") (name "/LED_B_mcu") (class "Default")
      (node (ref "DD10") (pin "2") (pinfunction "A_2") (pintype "passive"))
      (node (ref "DD3") (pin "38") (pinfunction "PA15_38") (pintype "passive"))
    )
    (net (code "15") (name "/LED_G") (class "Default")
      (node (ref "DD8") (pin "4") (pinfunction "Y_4") (pintype "passive"))
      (node (ref "R49") (pin "2") (pinfunction "2_2") (pintype "passive"))
      (node (ref "XP1") (pin "12") (pinfunction "12_12") (pintype "passive"))
    )
    (net (code "16") (name "/LED_G_mcu") (class "Default")
      (node (ref "DD3") (pin "37") (pinfunction "PA14_37") (pintype "passive"))
      (node (ref "DD8") (pin "2") (pinfunction "A_2") (pintype "passive"))
    )
    (net (code "17") (name "/LED_P_B") (class "Default")
      (node (ref "DD13") (pin "4") (pinfunction "Y_4") (pintype "passive"))
      (node (ref "XP3") (pin "11") (pinfunction "11_11") (pintype "passive"))
    )
    (net (code "18") (name "/LED_P_B_mcu") (class "Default")
      (node (ref "DD13") (pin "2") (pinfunction "A_2") (pintype "passive"))
      (node (ref "DD3") (pin "45") (pinfunction "PB8_45") (pintype "passive"))
    )
    (net (code "19") (name "/LED_P_G") (class "Default")
      (node (ref "DD12") (pin "4") (pinfunction "Y_4") (pintype "passive"))
      (node (ref "XP3") (pin "12") (pinfunction "12_12") (pintype "passive"))
    )
    (net (code "20") (name "/LED_P_G_mcu") (class "Default")
      (node (ref "DD12") (pin "2") (pinfunction "A_2") (pintype "passive"))
      (node (ref "DD3") (pin "43") (pinfunction "PB7_43") (pintype "passive"))
    )
    (net (code "21") (name "/LED_P_R") (class "Default")
      (node (ref "DD11") (pin "4") (pinfunction "Y_4") (pintype "passive"))
      (node (ref "XP3") (pin "13") (pinfunction "13_13") (pintype "passive"))
    )
    (net (code "22") (name "/LED_P_R_mcu") (class "Default")
      (node (ref "DD11") (pin "2") (pinfunction "A_2") (pintype "passive"))
      (node (ref "DD3") (pin "42") (pinfunction "PB6_42") (pintype "passive"))
    )
    (net (code "23") (name "/LED_R") (class "Default")
      (node (ref "DD9") (pin "4") (pinfunction "Y_4") (pintype "passive"))
      (node (ref "R48") (pin "2") (pinfunction "2_2") (pintype "passive"))
      (node (ref "XP1") (pin "11") (pinfunction "11_11") (pintype "passive"))
    )
    (net (code "24") (name "/LED_R_mcu") (class "Default")
      (node (ref "DD3") (pin "34") (pinfunction "PA13_34") (pintype "passive"))
      (node (ref "DD9") (pin "2") (pinfunction "A_2") (pintype "passive"))
    )
    (net (code "25") (name "/NRST") (class "Default")
      (node (ref "C15") (pin "2") (pinfunction "2_2") (pintype "passive"))
      (node (ref "DD3") (pin "7") (pinfunction "NRST_7") (pintype "passive"))
      (node (ref "R30") (pin "2") (pinfunction "2_2") (pintype "passive"))
      (node (ref "XP5") (pin "3") (pinfunction "3_3") (pintype "passive"))
    )
    (net (code "26") (name "/RTC_SCL") (class "Default")
      (node (ref "DD1") (pin "6") (pinfunction "SCL_6") (pintype "power_in"))
      (node (ref "DD3") (pin "21") (pinfunction "PB10_21") (pintype "passive"))
      (node (ref "R6") (pin "2") (pinfunction "2_2") (pintype "passive"))
    )
    (net (code "27") (name "/RTC_SDA") (class "Default")
      (node (ref "DD1") (pin "5") (pinfunction "SDA_5") (pintype "power_in"))
      (node (ref "DD3") (pin "22") (pinfunction "PB11_22") (pintype "passive"))
      (node (ref "R7") (pin "2") (pinfunction "2_2") (pintype "passive"))
    )
    (net (code "28") (name "/RTC_SQW") (class "Default")
      (node (ref "DD1") (pin "7") (pinfunction "SQW/Vout_7") (pintype "power_in"))
      (node (ref "DD3") (pin "25") (pinfunction "PB12_25") (pintype "passive"))
      (node (ref "R8") (pin "2") (pinfunction "2_2") (pintype "passive"))
    )
    (net (code "29") (name "/T1_MCU_a0") (class "Default")
      (node (ref "DD3") (pin "29") (pinfunction "PA8_29") (pintype "passive"))
      (node (ref "DD4") (pin "2") (pinfunction "1A_2") (pintype "power_in"))
      (node (ref "R12") (pin "1") (pinfunction "1_1") (pintype "passive"))
      (node (ref "R15") (pin "2") (pinfunction "2_2") (pintype "passive"))
    )
    (net (code "30") (name "/T1_MCU_a1") (class "Default")
      (node (ref "DD3") (pin "28") (pinfunction "PB15_28") (pintype "passive"))
      (node (ref "DD4") (pin "5") (pinfunction "2A_5") (pintype "power_in"))
      (node (ref "R17") (pin "1") (pinfunction "1_1") (pintype "passive"))
      (node (ref "R19") (pin "2") (pinfunction "2_2") (pintype "passive"))
    )
    (net (code "31") (name "/T1_MCU_a2") (class "Default")
      (node (ref "DD3") (pin "27") (pinfunction "PB14_27") (pintype "passive"))
      (node (ref "DD4") (pin "9") (pinfunction "3A_9") (pintype "power_in"))
      (node (ref "R21") (pin "1") (pinfunction "1_1") (pintype "passive"))
      (node (ref "R23") (pin "2") (pinfunction "2_2") (pintype "passive"))
    )
    (net (code "32") (name "/T1_MCU_a3") (class "Default")
      (node (ref "DD3") (pin "26") (pinfunction "PB13_26") (pintype "passive"))
      (node (ref "DD4") (pin "12") (pinfunction "4A_12") (pintype "power_in"))
      (node (ref "R25") (pin "1") (pinfunction "1_1") (pintype "passive"))
      (node (ref "R27") (pin "2") (pinfunction "2_2") (pintype "passive"))
    )
    (net (code "33") (name "/T1_a0") (class "Default")
      (node (ref "DD4") (pin "3") (pinfunction "1Y_3") (pintype "power_in"))
      (node (ref "XP1") (pin "3") (pinfunction "3_3") (pintype "passive"))
    )
    (net (code "34") (name "/T1_a1") (class "Default")
      (node (ref "DD4") (pin "6") (pinfunction "2Y_6") (pintype "power_in"))
      (node (ref "XP1") (pin "4") (pinfunction "4_4") (pintype "passive"))
    )
    (net (code "35") (name "/T1_a2") (class "Default")
      (node (ref "DD4") (pin "8") (pinfunction "3Y_8") (pintype "power_in"))
      (node (ref "XP1") (pin "5") (pinfunction "5_5") (pintype "passive"))
    )
    (net (code "36") (name "/T1_a3") (class "Default")
      (node (ref "DD4") (pin "11") (pinfunction "4Y_11") (pintype "power_in"))
      (node (ref "XP1") (pin "6") (pinfunction "6_6") (pintype "passive"))
    )
    (net (code "37") (name "/T2_MCU_a0") (class "Default")
      (node (ref "DD3") (pin "33") (pinfunction "PA12_33") (pintype "passive"))
      (node (ref "DD5") (pin "2") (pinfunction "1A_2") (pintype "power_in"))
      (node (ref "R13") (pin "1") (pinfunction "1_1") (pintype "passive"))
      (node (ref "R16") (pin "2") (pinfunction "2_2") (pintype "passive"))
    )
    (net (code "38") (name "/T2_MCU_a1") (class "Default")
      (node (ref "DD3") (pin "32") (pinfunction "PA11_32") (pintype "passive"))
      (node (ref "DD5") (pin "5") (pinfunction "2A_5") (pintype "power_in"))
      (node (ref "R18") (pin "1") (pinfunction "1_1") (pintype "passive"))
      (node (ref "R20") (pin "2") (pinfunction "2_2") (pintype "passive"))
    )
    (net (code "39") (name "/T2_MCU_a2") (class "Default")
      (node (ref "DD3") (pin "31") (pinfunction "PA10_31") (pintype "passive"))
      (node (ref "DD5") (pin "9") (pinfunction "3A_9") (pintype "power_in"))
      (node (ref "R22") (pin "1") (pinfunction "1_1") (pintype "passive"))
      (node (ref "R24") (pin "2") (pinfunction "2_2") (pintype "passive"))
    )
    (net (code "40") (name "/T2_MCU_a3") (class "Default")
      (node (ref "DD3") (pin "30") (pinfunction "PA9_30") (pintype "passive"))
      (node (ref "DD5") (pin "12") (pinfunction "4A_12") (pintype "power_in"))
      (node (ref "R26") (pin "1") (pinfunction "1_1") (pintype "passive"))
      (node (ref "R28") (pin "2") (pinfunction "2_2") (pintype "passive"))
    )
    (net (code "41") (name "/T2_a0") (class "Default")
      (node (ref "DD5") (pin "3") (pinfunction "1Y_3") (pintype "power_in"))
      (node (ref "XP1") (pin "7") (pinfunction "7_7") (pintype "passive"))
    )
    (net (code "42") (name "/T2_a1") (class "Default")
      (node (ref "DD5") (pin "6") (pinfunction "2Y_6") (pintype "power_in"))
      (node (ref "XP1") (pin "8") (pinfunction "8_8") (pintype "passive"))
    )
    (net (code "43") (name "/T2_a2") (class "Default")
      (node (ref "DD5") (pin "8") (pinfunction "3Y_8") (pintype "power_in"))
      (node (ref "XP1") (pin "9") (pinfunction "9_9") (pintype "passive"))
    )
    (net (code "44") (name "/T2_a3") (class "Default")
      (node (ref "DD5") (pin "11") (pinfunction "4Y_11") (pintype "power_in"))
      (node (ref "XP1") (pin "10") (pinfunction "10_10") (pintype "passive"))
    )
    (net (code "45") (name "/T3_MCU_a0") (class "Default")
      (node (ref "DD3") (pin "4") (pinfunction "PC15-OSC32_OUT_4") (pintype "passive"))
      (node (ref "DD6") (pin "2") (pinfunction "1A_2") (pintype "power_in"))
      (node (ref "R31") (pin "1") (pinfunction "1_1") (pintype "passive"))
      (node (ref "R33") (pin "2") (pinfunction "2_2") (pintype "passive"))
    )
    (net (code "46") (name "/T3_MCU_a1") (class "Default")
      (node (ref "DD3") (pin "3") (pinfunction "PC14-OSC32_IN_3") (pintype "passive"))
      (node (ref "DD6") (pin "5") (pinfunction "2A_5") (pintype "power_in"))
      (node (ref "R35") (pin "1") (pinfunction "1_1") (pintype "passive"))
      (node (ref "R37") (pin "2") (pinfunction "2_2") (pintype "passive"))
    )
    (net (code "47") (name "/T3_MCU_a2") (class "Default")
      (node (ref "DD3") (pin "2") (pinfunction "PC13-TAMPER-RTC_2") (pintype "passive"))
      (node (ref "DD6") (pin "9") (pinfunction "3A_9") (pintype "power_in"))
      (node (ref "R39") (pin "1") (pinfunction "1_1") (pintype "passive"))
      (node (ref "R41") (pin "2") (pinfunction "2_2") (pintype "passive"))
    )
    (net (code "48") (name "/T3_MCU_a3") (class "Default")
      (node (ref "DD3") (pin "46") (pinfunction "PB9_46") (pintype "passive"))
      (node (ref "DD6") (pin "12") (pinfunction "4A_12") (pintype "power_in"))
      (node (ref "R44") (pin "1") (pinfunction "1_1") (pintype "passive"))
      (node (ref "R46") (pin "2") (pinfunction "2_2") (pintype "passive"))
    )
    (net (code "49") (name "/T3_a0") (class "Default")
      (node (ref "DD6") (pin "3") (pinfunction "1Y_3") (pintype "power_in"))
      (node (ref "XP3") (pin "7") (pinfunction "7_7") (pintype "passive"))
    )
    (net (code "50") (name "/T3_a1") (class "Default")
      (node (ref "DD6") (pin "6") (pinfunction "2Y_6") (pintype "power_in"))
      (node (ref "XP3") (pin "8") (pinfunction "8_8") (pintype "passive"))
    )
    (net (code "51") (name "/T3_a2") (class "Default")
      (node (ref "DD6") (pin "8") (pinfunction "3Y_8") (pintype "power_in"))
      (node (ref "XP3") (pin "9") (pinfunction "9_9") (pintype "passive"))
    )
    (net (code "52") (name "/T3_a3") (class "Default")
      (node (ref "DD6") (pin "11") (pinfunction "4Y_11") (pintype "power_in"))
      (node (ref "XP3") (pin "10") (pinfunction "10_10") (pintype "passive"))
    )
    (net (code "53") (name "/T4_MCU_a0") (class "Default")
      (node (ref "DD3") (pin "13") (pinfunction "PA3_13") (pintype "passive"))
      (node (ref "DD7") (pin "2") (pinfunction "1A_2") (pintype "power_in"))
      (node (ref "R32") (pin "1") (pinfunction "1_1") (pintype "passive"))
      (node (ref "R34") (pin "2") (pinfunction "2_2") (pintype "passive"))
    )
    (net (code "54") (name "/T4_MCU_a1") (class "Default")
      (node (ref "DD3") (pin "12") (pinfunction "PA2_12") (pintype "passive"))
      (node (ref "DD7") (pin "5") (pinfunction "2A_5") (pintype "power_in"))
      (node (ref "R36") (pin "1") (pinfunction "1_1") (pintype "passive"))
      (node (ref "R38") (pin "2") (pinfunction "2_2") (pintype "passive"))
    )
    (net (code "55") (name "/T4_MCU_a2") (class "Default")
      (node (ref "DD3") (pin "11") (pinfunction "PA1_11") (pintype "passive"))
      (node (ref "DD7") (pin "9") (pinfunction "3A_9") (pintype "power_in"))
      (node (ref "R40") (pin "1") (pinfunction "1_1") (pintype "passive"))
      (node (ref "R42") (pin "2") (pinfunction "2_2") (pintype "passive"))
    )
    (net (code "56") (name "/T4_MCU_a3") (class "Default")
      (node (ref "DD3") (pin "10") (pinfunction "PA0-WKUP_10") (pintype "passive"))
      (node (ref "DD7") (pin "12") (pinfunction "4A_12") (pintype "power_in"))
      (node (ref "R45") (pin "1") (pinfunction "1_1") (pintype "passive"))
      (node (ref "R47") (pin "2") (pinfunction "2_2") (pintype "passive"))
    )
    (net (code "57") (name "/T4_a0") (class "Default")
      (node (ref "DD7") (pin "3") (pinfunction "1Y_3") (pintype "power_in"))
      (node (ref "XP3") (pin "3") (pinfunction "3_3") (pintype "passive"))
    )
    (net (code "58") (name "/T4_a1") (class "Default")
      (node (ref "DD7") (pin "6") (pinfunction "2Y_6") (pintype "power_in"))
      (node (ref "XP3") (pin "4") (pinfunction "4_4") (pintype "passive"))
    )
    (net (code "59") (name "/T4_a2") (class "Default")
      (node (ref "DD7") (pin "8") (pinfunction "3Y_8") (pintype "power_in"))
      (node (ref "XP3") (pin "5") (pinfunction "5_5") (pintype "passive"))
    )
    (net (code "60") (name "/T4_a3") (class "Default")
      (node (ref "DD7") (pin "11") (pinfunction "4Y_11") (pintype "power_in"))
      (node (ref "XP3") (pin "6") (pinfunction "6_6") (pintype "passive"))
    )
    (net (code "61") (name "GND") (class "Default")
      (node (ref "BL1") (pin "1") (pinfunction "GND_1") (pintype "passive"))
      (node (ref "C1") (pin "2") (pinfunction "2_2") (pintype "passive"))
      (node (ref "C10") (pin "1") (pinfunction "1_1") (pintype "passive"))
      (node (ref "C11") (pin "2") (pinfunction "2_2") (pintype "passive"))
      (node (ref "C12") (pin "2") (pinfunction "2_2") (pintype "passive"))
      (node (ref "C13") (pin "1") (pinfunction "1_1") (pintype "passive"))
      (node (ref "C14") (pin "1") (pinfunction "1_1") (pintype "passive"))
      (node (ref "C15") (pin "1") (pinfunction "1_1") (pintype "passive"))
      (node (ref "C16") (pin "1") (pinfunction "1_1") (pintype "passive"))
      (node (ref "C17") (pin "1") (pinfunction "1_1") (pintype "passive"))
      (node (ref "C18") (pin "1") (pinfunction "1_1") (pintype "passive"))
      (node (ref "C19") (pin "1") (pinfunction "1_1") (pintype "passive"))
      (node (ref "C2") (pin "2") (pinfunction "2_2") (pintype "passive"))
      (node (ref "C20") (pin "1") (pinfunction "1_1") (pintype "passive"))
      (node (ref "C21") (pin "1") (pinfunction "1_1") (pintype "passive"))
      (node (ref "C22") (pin "1") (pinfunction "1_1") (pintype "passive"))
      (node (ref "C23") (pin "1") (pinfunction "1_1") (pintype "passive"))
      (node (ref "C24") (pin "1") (pinfunction "1_1") (pintype "passive"))
      (node (ref "C25") (pin "1") (pinfunction "1_1") (pintype "passive"))
      (node (ref "C26") (pin "1") (pinfunction "1_1") (pintype "passive"))
      (node (ref "C27") (pin "1") (pinfunction "1_1") (pintype "passive"))
      (node (ref "C28") (pin "1") (pinfunction "1_1") (pintype "passive"))
      (node (ref "C29") (pin "1") (pinfunction "1_1") (pintype "passive"))
      (node (ref "C3") (pin "1") (pinfunction "1_1") (pintype "passive"))
      (node (ref "C30") (pin "1") (pinfunction "1_1") (pintype "passive"))
      (node (ref "C31") (pin "1") (pinfunction "1_1") (pintype "passive"))
      (node (ref "C4") (pin "1") (pinfunction "1_1") (pintype "passive"))
      (node (ref "C5") (pin "1") (pinfunction "1_1") (pintype "passive"))
      (node (ref "C6") (pin "1") (pinfunction "1_1") (pintype "passive"))
      (node (ref "C7") (pin "2") (pinfunction "2_2") (pintype "passive"))
      (node (ref "C8") (pin "2") (pinfunction "2_2") (pintype "passive"))
      (node (ref "C9") (pin "1") (pinfunction "1_1") (pintype "passive"))
      (node (ref "DA1") (pin "1") (pinfunction "GND_1") (pintype "passive"))
      (node (ref "DA2") (pin "1") (pinfunction "GND_1") (pintype "passive"))
      (node (ref "DD1") (pin "4") (pinfunction "Vss_4") (pintype "power_in"))
      (node (ref "DD10") (pin "3") (pinfunction "GND_3") (pintype "passive"))
      (node (ref "DD11") (pin "3") (pinfunction "GND_3") (pintype "passive"))
      (node (ref "DD12") (pin "3") (pinfunction "GND_3") (pintype "passive"))
      (node (ref "DD13") (pin "3") (pinfunction "GND_3") (pintype "passive"))
      (node (ref "DD2") (pin "4") (pinfunction "GND_4") (pintype "power_in"))
      (node (ref "DD3") (pin "23") (pinfunction "VSS_1_23") (pintype "power_in"))
      (node (ref "DD3") (pin "35") (pinfunction "VSS_2_35") (pintype "power_in"))
      (node (ref "DD3") (pin "47") (pinfunction "VSS_3_47") (pintype "power_in"))
      (node (ref "DD3") (pin "8") (pinfunction "VSSA_8") (pintype "power_in"))
      (node (ref "DD4") (pin "7") (pinfunction "GND_7") (pintype "power_in"))
      (node (ref "DD5") (pin "7") (pinfunction "GND_7") (pintype "power_in"))
      (node (ref "DD6") (pin "7") (pinfunction "GND_7") (pintype "power_in"))
      (node (ref "DD7") (pin "7") (pinfunction "GND_7") (pintype "power_in"))
      (node (ref "DD8") (pin "3") (pinfunction "GND_3") (pintype "passive"))
      (node (ref "DD9") (pin "3") (pinfunction "GND_3") (pintype "passive"))
      (node (ref "GB1") (pin "2") (pinfunction "-_2") (pintype "passive"))
      (node (ref "R10") (pin "2") (pinfunction "2_2") (pintype "passive"))
      (node (ref "R15") (pin "1") (pinfunction "1_1") (pintype "passive"))
      (node (ref "R16") (pin "1") (pinfunction "1_1") (pintype "passive"))
      (node (ref "R19") (pin "1") (pinfunction "1_1") (pintype "passive"))
      (node (ref "R20") (pin "1") (pinfunction "1_1") (pintype "passive"))
      (node (ref "R23") (pin "1") (pinfunction "1_1") (pintype "passive"))
      (node (ref "R24") (pin "1") (pinfunction "1_1") (pintype "passive"))
      (node (ref "R27") (pin "1") (pinfunction "1_1") (pintype "passive"))
      (node (ref "R28") (pin "1") (pinfunction "1_1") (pintype "passive"))
      (node (ref "R29") (pin "2") (pinfunction "2_2") (pintype "passive"))
      (node (ref "R3") (pin "1") (pinfunction "1_1") (pintype "passive"))
      (node (ref "R33") (pin "1") (pinfunction "1_1") (pintype "passive"))
      (node (ref "R34") (pin "1") (pinfunction "1_1") (pintype "passive"))
      (node (ref "R37") (pin "1") (pinfunction "1_1") (pintype "passive"))
      (node (ref "R38") (pin "1") (pinfunction "1_1") (pintype "passive"))
      (node (ref "R4") (pin "1") (pinfunction "1_1") (pintype "passive"))
      (node (ref "R41") (pin "1") (pinfunction "1_1") (pintype "passive"))
      (node (ref "R42") (pin "1") (pinfunction "1_1") (pintype "passive"))
      (node (ref "R46") (pin "1") (pinfunction "1_1") (pintype "passive"))
      (node (ref "R47") (pin "1") (pinfunction "1_1") (pintype "passive"))
      (node (ref "R50") (pin "2") (pinfunction "2_2") (pintype "passive"))
      (node (ref "R51") (pin "1") (pinfunction "1_1") (pintype "passive"))
      (node (ref "U1") (pin "4") (pinfunction "GND_4") (pintype "passive"))
      (node (ref "VT1") (pin "3") (pinfunction "S_3") (pintype "passive"))
      (node (ref "VT2") (pin "1") (pinfunction "К_1") (pintype "passive"))
      (node (ref "XP1") (pin "1") (pinfunction "1_1") (pintype "passive"))
      (node (ref "XP2") (pin "2") (pinfunction "2_2") (pintype "passive"))
      (node (ref "XP2") (pin "3") (pinfunction "3_3") (pintype "passive"))
      (node (ref "XP3") (pin "1") (pinfunction "1_1") (pintype "passive"))
      (node (ref "XP4") (pin "2") (pinfunction "2_2") (pintype "passive"))
      (node (ref "XP5") (pin "4") (pinfunction "4_4") (pintype "passive"))
    )
    (net (code "62") (name "Net-(DD1-Vbat)") (class "Default")
      (node (ref "DD1") (pin "3") (pinfunction "Vbat_3") (pintype "power_in"))
      (node (ref "GB1") (pin "1") (pinfunction "+_1") (pintype "passive"))
    )
    (net (code "63") (name "Net-(DD1-X1)") (class "Default")
      (node (ref "BQ1") (pin "2") (pinfunction "2_2") (pintype "passive"))
      (node (ref "DD1") (pin "1") (pinfunction "X1_1") (pintype "power_in"))
    )
    (net (code "64") (name "Net-(DD1-X2)") (class "Default")
      (node (ref "BQ1") (pin "1") (pinfunction "1_1") (pintype "passive"))
      (node (ref "DD1") (pin "2") (pinfunction "X2_2") (pintype "power_in"))
    )
    (net (code "65") (name "Net-(DD2-SERMODE)") (class "Default")
      (node (ref "DD2") (pin "7") (pinfunction "SERMODE_7") (pintype "power_in"))
      (node (ref "R10") (pin "1") (pinfunction "1_1") (pintype "passive"))
      (node (ref "R9") (pin "2") (pinfunction "2_2") (pintype "passive"))
    )
    (net (code "66") (name "Net-(DD3A-PD0-OSC_IN)") (class "Default")
      (node (ref "BQ2") (pin "3") (pinfunction "3_3") (pintype "passive"))
      (node (ref "C16") (pin "2") (pinfunction "2_2") (pintype "passive"))
      (node (ref "DD3") (pin "5") (pinfunction "PD0-OSC_IN_5") (pintype "passive"))
    )
    (net (code "67") (name "Net-(DD3A-PD1-OSC_OUT)") (class "Default")
      (node (ref "BQ2") (pin "1") (pinfunction "1_1") (pintype "passive"))
      (node (ref "C17") (pin "2") (pinfunction "2_2") (pintype "passive"))
      (node (ref "DD3") (pin "6") (pinfunction "PD1-OSC_OUT_6") (pintype "passive"))
    )
    (net (code "68") (name "Net-(DD3B-VBAT)") (class "Default")
      (node (ref "DD3") (pin "1") (pinfunction "VBAT_1") (pintype "power_in"))
      (node (ref "R43") (pin "2") (pinfunction "2_2") (pintype "passive"))
    )
    (net (code "69") (name "Net-(DD8-OE)") (class "Default")
      (node (ref "DD8") (pin "1") (pinfunction "OE_1") (pintype "passive"))
      (node (ref "R52") (pin "2") (pinfunction "2_2") (pintype "passive"))
    )
    (net (code "70") (name "Net-(DD9-OE)") (class "Default")
      (node (ref "DD9") (pin "1") (pinfunction "OE_1") (pintype "passive"))
      (node (ref "R53") (pin "2") (pinfunction "2_2") (pintype "passive"))
    )
    (net (code "71") (name "Net-(DD10-OE)") (class "Default")
      (node (ref "DD10") (pin "1") (pinfunction "OE_1") (pintype "passive"))
      (node (ref "R54") (pin "2") (pinfunction "2_2") (pintype "passive"))
    )
    (net (code "72") (name "Net-(DD11-OE)") (class "Default")
      (node (ref "DD11") (pin "1") (pinfunction "OE_1") (pintype "passive"))
      (node (ref "R55") (pin "2") (pinfunction "2_2") (pintype "passive"))
    )
    (net (code "73") (name "Net-(DD12-OE)") (class "Default")
      (node (ref "DD12") (pin "1") (pinfunction "OE_1") (pintype "passive"))
      (node (ref "R56") (pin "2") (pinfunction "2_2") (pintype "passive"))
    )
    (net (code "74") (name "Net-(DD13-OE)") (class "Default")
      (node (ref "DD13") (pin "1") (pinfunction "OE_1") (pintype "passive"))
      (node (ref "R57") (pin "2") (pinfunction "2_2") (pintype "passive"))
    )
    (net (code "75") (name "Net-(R2-Pad1)") (class "Default")
      (node (ref "R2") (pin "1") (pinfunction "1_1") (pintype "passive"))
      (node (ref "R5") (pin "2") (pinfunction "2_2") (pintype "passive"))
    )
    (net (code "76") (name "Net-(R11-Pad1)") (class "Default")
      (node (ref "R11") (pin "1") (pinfunction "1_1") (pintype "passive"))
      (node (ref "XP6") (pin "1") (pinfunction "1_1") (pintype "passive"))
    )
    (net (code "77") (name "Net-(R14-Pad1)") (class "Default")
      (node (ref "R14") (pin "1") (pinfunction "1_1") (pintype "passive"))
      (node (ref "XP6") (pin "2") (pinfunction "2_2") (pintype "passive"))
    )
    (net (code "78") (name "Net-(R48-Pad1)") (class "Default")
      (node (ref "R48") (pin "1") (pinfunction "1_1") (pintype "passive"))
      (node (ref "XP5") (pin "1") (pinfunction "1_1") (pintype "passive"))
    )
    (net (code "79") (name "Net-(R49-Pad1)") (class "Default")
      (node (ref "R49") (pin "1") (pinfunction "1_1") (pintype "passive"))
      (node (ref "XP5") (pin "2") (pinfunction "2_2") (pintype "passive"))
    )
    (net (code "80") (name "Net-(U1-CII)") (class "Default")
      (node (ref "C5") (pin "2") (pinfunction "2_2") (pintype "passive"))
      (node (ref "R3") (pin "2") (pinfunction "2_2") (pintype "passive"))
      (node (ref "R5") (pin "1") (pinfunction "1_1") (pintype "passive"))
      (node (ref "U1") (pin "5") (pinfunction "CII_5") (pintype "passive"))
    )
    (net (code "81") (name "Net-(U1-I_pk)") (class "Default")
      (node (ref "L1") (pin "1") (pinfunction "1_1") (pintype "passive"))
      (node (ref "R1") (pin "2") (pinfunction "2_2") (pintype "passive"))
      (node (ref "U1") (pin "7") (pinfunction "I_pk_7") (pintype "passive"))
    )
    (net (code "82") (name "Net-(U1-SWE)") (class "Default")
      (node (ref "R4") (pin "2") (pinfunction "2_2") (pintype "passive"))
      (node (ref "U1") (pin "2") (pinfunction "SWE_2") (pintype "passive"))
      (node (ref "VD2") (pin "1") (pinfunction "A_1") (pintype "passive"))
      (node (ref "VT2") (pin "2") (pinfunction "Б_2") (pintype "passive"))
    )
    (net (code "83") (name "Net-(U1-TC)") (class "Default")
      (node (ref "C4") (pin "2") (pinfunction "2_2") (pintype "passive"))
      (node (ref "U1") (pin "3") (pinfunction "TC_3") (pintype "passive"))
    )
    (net (code "84") (name "Net-(VD1-A)") (class "Default")
      (node (ref "L1") (pin "2") (pinfunction "2_2") (pintype "passive"))
      (node (ref "VD1") (pin "1") (pinfunction "A_1") (pintype "passive"))
      (node (ref "VT1") (pin "2") (pinfunction "D_2") (pintype "passive"))
    )
    (net (code "85") (name "Net-(VD2-K)") (class "Default")
      (node (ref "VD2") (pin "2") (pinfunction "K_2") (pintype "passive"))
      (node (ref "VT1") (pin "1") (pinfunction "G_1") (pintype "passive"))
      (node (ref "VT2") (pin "3") (pinfunction "Э_3") (pintype "passive"))
    )
    (net (code "86") (name "unconnected-(DD3A-PB0-Pad18)") (class "Default")
      (node (ref "DD3") (pin "18") (pinfunction "PB0_18") (pintype "passive"))
    )
    (net (code "87") (name "unconnected-(DD3A-PB1-Pad19)") (class "Default")
      (node (ref "DD3") (pin "19") (pinfunction "PB1_19") (pintype "passive"))
    )
    (net (code "88") (name "unconnected-(DD3A-PB2-Pad20)") (class "Default")
      (node (ref "DD3") (pin "20") (pinfunction "PB2_20") (pintype "passive"))
    )
  )
)
